# stm32103c8t6-v3.net
KiCad netlist of a schematic drawn in EAGLE
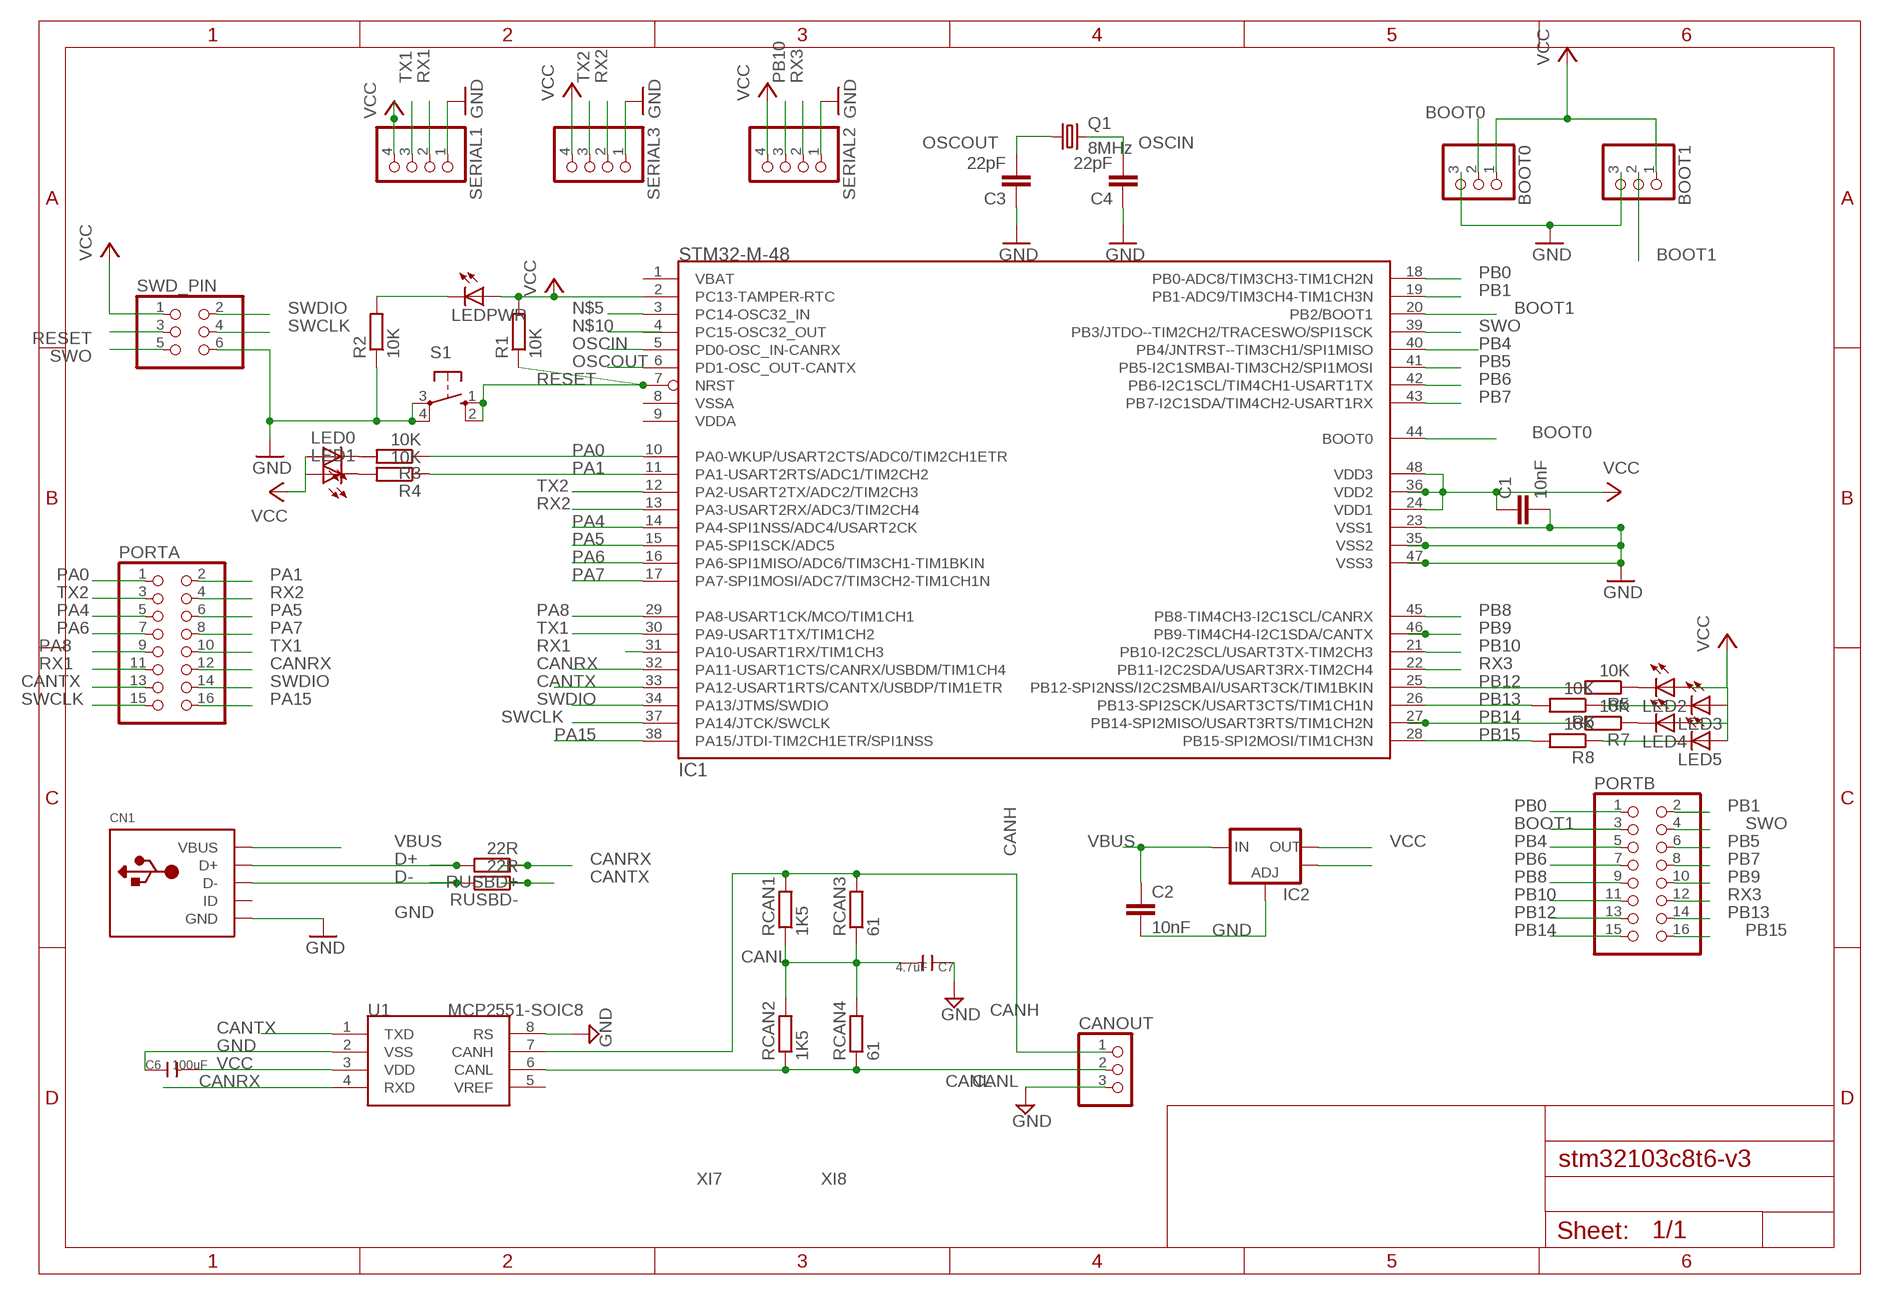
[diagram p0: schematic, sheet 1]

(export (version "E")
  (design (tool "Eeschema 10.0.6"))
  (components
    (comp (ref "BOOT0")
      (value "PINHD-1X3")
      (footprint "eagle-import:1X03")
      (libsource (lib "eagle-import") (part "PINHD-1X3"))
    )
    (comp (ref "BOOT1")
      (value "PINHD-1X3")
      (footprint "eagle-import:1X03")
      (libsource (lib "eagle-import") (part "PINHD-1X3"))
    )
    (comp (ref "C1")
      (value "10nF")
      (footprint "eagle-import:C1210")
      (libsource (lib "eagle-import") (part "C-EUC1210"))
    )
    (comp (ref "C2")
      (value "10nF")
      (footprint "eagle-import:C1206")
      (libsource (lib "eagle-import") (part "C-EUC1206"))
    )
    (comp (ref "C3")
      (value "22pF")
      (footprint "eagle-import:C1210")
      (libsource (lib "eagle-import") (part "C-EUC1210"))
    )
    (comp (ref "C4")
      (value "22pF")
      (footprint "eagle-import:C1210")
      (libsource (lib "eagle-import") (part "C-EUC1210"))
    )
    (comp (ref "C6")
      (value "100uF")
      (footprint "eagle-import:C1206")
      (libsource (lib "eagle-import") (part "C-1206"))
    )
    (comp (ref "C7")
      (value "4.7uF")
      (footprint "eagle-import:C1206")
      (libsource (lib "eagle-import") (part "C-1206"))
    )
    (comp (ref "CANOUT")
      (value "PINHD-1X3")
      (footprint "eagle-import:1X03")
      (libsource (lib "eagle-import") (part "PINHD-1X3"))
    )
    (comp (ref "CN1")
      (value "USBTHM")
      (footprint "eagle-import:USB-MINIB-THM")
      (libsource (lib "eagle-import") (part "USBTHM"))
    )
    (comp (ref "IC1")
      (value "STM32-M-48")
      (footprint "eagle-import:LQFP48")
      (libsource (lib "eagle-import") (part "STM32-M-48"))
    )
    (comp (ref "IC2")
      (value "V_REG_LM1117SOT223")
      (footprint "eagle-import:SOT223")
      (libsource (lib "eagle-import") (part "V_REG_LM1117SOT223"))
    )
    (comp (ref "LED0")
      (value "LEDSMT1206")
      (footprint "eagle-import:1206")
      (libsource (lib "eagle-import") (part "LEDSMT1206"))
    )
    (comp (ref "LED1")
      (value "LEDSMT1206")
      (footprint "eagle-import:1206")
      (libsource (lib "eagle-import") (part "LEDSMT1206"))
    )
    (comp (ref "LED2")
      (value "LEDSMT1206")
      (footprint "eagle-import:1206")
      (libsource (lib "eagle-import") (part "LEDSMT1206"))
    )
    (comp (ref "LED3")
      (value "LEDSMT1206")
      (footprint "eagle-import:1206")
      (libsource (lib "eagle-import") (part "LEDSMT1206"))
    )
    (comp (ref "LED4")
      (value "LEDSMT1206")
      (footprint "eagle-import:1206")
      (libsource (lib "eagle-import") (part "LEDSMT1206"))
    )
    (comp (ref "LED5")
      (value "LEDSMT1206")
      (footprint "eagle-import:1206")
      (libsource (lib "eagle-import") (part "LEDSMT1206"))
    )
    (comp (ref "LEDPWR")
      (value "LEDSMT1206")
      (footprint "eagle-import:1206")
      (libsource (lib "eagle-import") (part "LEDSMT1206"))
    )
    (comp (ref "PORTA")
      (value "PINHD-2X8")
      (footprint "eagle-import:2X08")
      (libsource (lib "eagle-import") (part "PINHD-2X8"))
    )
    (comp (ref "PORTB")
      (value "PINHD-2X8")
      (footprint "eagle-import:2X08")
      (libsource (lib "eagle-import") (part "PINHD-2X8"))
    )
    (comp (ref "Q1")
      (value "8MHz")
      (footprint "eagle-import:HC49_S")
      (libsource (lib "eagle-import") (part "CRYSTALHC49S"))
    )
    (comp (ref "R1")
      (value "10K")
      (footprint "eagle-import:R1206")
      (libsource (lib "eagle-import") (part "R-EU_R1206"))
    )
    (comp (ref "R2")
      (value "10K")
      (footprint "eagle-import:R1206")
      (libsource (lib "eagle-import") (part "R-EU_R1206"))
    )
    (comp (ref "R3")
      (value "10K")
      (footprint "eagle-import:R1206")
      (libsource (lib "eagle-import") (part "R-EU_R1206"))
    )
    (comp (ref "R4")
      (value "10K")
      (footprint "eagle-import:R1206")
      (libsource (lib "eagle-import") (part "R-EU_R1206"))
    )
    (comp (ref "R5")
      (value "10K")
      (footprint "eagle-import:R1206")
      (libsource (lib "eagle-import") (part "R-EU_R1206"))
    )
    (comp (ref "R6")
      (value "10K")
      (footprint "eagle-import:R1206")
      (libsource (lib "eagle-import") (part "R-EU_R1206"))
    )
    (comp (ref "R7")
      (value "10K")
      (footprint "eagle-import:R1206")
      (libsource (lib "eagle-import") (part "R-EU_R1206"))
    )
    (comp (ref "R8")
      (value "10K")
      (footprint "eagle-import:R1206")
      (libsource (lib "eagle-import") (part "R-EU_R1206"))
    )
    (comp (ref "RCAN1")
      (value "1K5")
      (footprint "eagle-import:R1206")
      (libsource (lib "eagle-import") (part "R-EU_R1206"))
    )
    (comp (ref "RCAN2")
      (value "1K5")
      (footprint "eagle-import:R1206")
      (libsource (lib "eagle-import") (part "R-EU_R1206"))
    )
    (comp (ref "RCAN3")
      (value "61")
      (footprint "eagle-import:R1206")
      (libsource (lib "eagle-import") (part "R-EU_R1206"))
    )
    (comp (ref "RCAN4")
      (value "61")
      (footprint "eagle-import:R1206")
      (libsource (lib "eagle-import") (part "R-EU_R1206"))
    )
    (comp (ref "RUSBD+")
      (value "22R")
      (footprint "eagle-import:R1206")
      (libsource (lib "eagle-import") (part "R-EU_R1206"))
    )
    (comp (ref "RUSBD-")
      (value "22R")
      (footprint "eagle-import:R1206")
      (libsource (lib "eagle-import") (part "R-EU_R1206"))
    )
    (comp (ref "S1")
      (value "10-XX")
      (footprint "eagle-import:B3F-10XX")
      (fields (field (name "MPN") "B3F-1000"))
      (libsource (lib "eagle-import") (part "10-XX"))
    )
    (comp (ref "SERIAL1")
      (value "PINHD-1X4")
      (footprint "eagle-import:1X04")
      (libsource (lib "eagle-import") (part "PINHD-1X4"))
    )
    (comp (ref "SERIAL2")
      (value "PINHD-1X4")
      (footprint "eagle-import:1X04")
      (libsource (lib "eagle-import") (part "PINHD-1X4"))
    )
    (comp (ref "SERIAL3")
      (value "PINHD-1X4")
      (footprint "eagle-import:1X04")
      (libsource (lib "eagle-import") (part "PINHD-1X4"))
    )
    (comp (ref "SWD_PIN")
      (value "PINHD-2X3")
      (footprint "eagle-import:2X03")
      (libsource (lib "eagle-import") (part "PINHD-2X3"))
    )
    (comp (ref "U1")
      (value "MCP2551-SOIC8")
      (footprint "eagle-import:SOIC8-6.0")
      (libsource (lib "eagle-import") (part "MCP2551-SOIC8"))
    )
  )
  (nets
    (net (code "1") (name "/BOOT0") (class "Default")
      (node (ref "BOOT0") (pin "2") (pinfunction "2_2") (pintype "passive"))
      (node (ref "IC1") (pin "44") (pinfunction "BOOT0_44") (pintype "input"))
    )
    (net (code "2") (name "/BOOT1") (class "Default")
      (node (ref "BOOT1") (pin "2") (pinfunction "2_2") (pintype "passive"))
      (node (ref "IC1") (pin "20") (pinfunction "PB2/BOOT1_20") (pintype "bidirectional"))
      (node (ref "PORTB") (pin "3") (pinfunction "3_3") (pintype "passive"))
    )
    (net (code "3") (name "/CANH") (class "Default")
      (node (ref "CANOUT") (pin "1") (pinfunction "1_1") (pintype "passive"))
      (node (ref "RCAN1") (pin "2") (pinfunction "2_2") (pintype "passive"))
      (node (ref "RCAN3") (pin "2") (pinfunction "2_2") (pintype "passive"))
      (node (ref "U1") (pin "7") (pinfunction "CANH_7") (pintype "bidirectional"))
    )
    (net (code "4") (name "/CANL") (class "Default")
      (node (ref "CANOUT") (pin "2") (pinfunction "2_2") (pintype "passive"))
      (node (ref "RCAN2") (pin "1") (pinfunction "1_1") (pintype "passive"))
      (node (ref "RCAN4") (pin "1") (pinfunction "1_1") (pintype "passive"))
      (node (ref "U1") (pin "6") (pinfunction "CANL_6") (pintype "bidirectional"))
    )
    (net (code "5") (name "/CANRX") (class "Default")
      (node (ref "IC1") (pin "32") (pinfunction "PA11-USART1CTS/CANRX/USBDM/TIM1CH4_32") (pintype "bidirectional"))
      (node (ref "PORTA") (pin "12") (pinfunction "12_12") (pintype "passive"))
      (node (ref "RUSBD+") (pin "1") (pinfunction "1_1") (pintype "passive"))
      (node (ref "U1") (pin "4") (pinfunction "RXD_4") (pintype "bidirectional"))
    )
    (net (code "6") (name "/CANTX") (class "Default")
      (node (ref "IC1") (pin "33") (pinfunction "PA12-USART1RTS/CANTX/USBDP/TIM1ETR_33") (pintype "bidirectional"))
      (node (ref "PORTA") (pin "13") (pinfunction "13_13") (pintype "passive"))
      (node (ref "RUSBD-") (pin "1") (pinfunction "1_1") (pintype "passive"))
      (node (ref "U1") (pin "1") (pinfunction "TXD_1") (pintype "bidirectional"))
    )
    (net (code "7") (name "/D+") (class "Default")
      (node (ref "CN1") (pin "D+") (pinfunction "D+_D+") (pintype "bidirectional"))
      (node (ref "RUSBD+") (pin "2") (pinfunction "2_2") (pintype "passive"))
    )
    (net (code "8") (name "/D-") (class "Default")
      (node (ref "CN1") (pin "D-") (pinfunction "D-_D-") (pintype "bidirectional"))
      (node (ref "RUSBD-") (pin "2") (pinfunction "2_2") (pintype "passive"))
    )
    (net (code "9") (name "/N$5") (class "Default")
      (node (ref "IC1") (pin "3") (pinfunction "PC14-OSC32_IN_3") (pintype "bidirectional"))
    )
    (net (code "11") (name "/OSCIN") (class "Default")
      (node (ref "C4") (pin "2") (pinfunction "2_2") (pintype "passive"))
      (node (ref "IC1") (pin "5") (pinfunction "PD0-OSC_IN-CANRX_5") (pintype "input"))
      (node (ref "Q1") (pin "2") (pinfunction "2_2") (pintype "passive"))
    )
    (net (code "12") (name "/OSCOUT") (class "Default")
      (node (ref "C3") (pin "2") (pinfunction "2_2") (pintype "passive"))
      (node (ref "IC1") (pin "6") (pinfunction "PD1-OSC_OUT-CANTX_6") (pintype "output"))
      (node (ref "Q1") (pin "1") (pinfunction "1_1") (pintype "passive"))
    )
    (net (code "13") (name "/PA0") (class "Default")
      (node (ref "IC1") (pin "10") (pinfunction "PA0-WKUP/USART2CTS/ADC0/TIM2CH1ETR_10") (pintype "bidirectional"))
      (node (ref "PORTA") (pin "1") (pinfunction "1_1") (pintype "passive"))
      (node (ref "R3") (pin "1") (pinfunction "1_1") (pintype "passive"))
    )
    (net (code "14") (name "/PA1") (class "Default")
      (node (ref "IC1") (pin "11") (pinfunction "PA1-USART2RTS/ADC1/TIM2CH2_11") (pintype "bidirectional"))
      (node (ref "PORTA") (pin "2") (pinfunction "2_2") (pintype "passive"))
      (node (ref "R4") (pin "1") (pinfunction "1_1") (pintype "passive"))
    )
    (net (code "15") (name "/PA4") (class "Default")
      (node (ref "IC1") (pin "14") (pinfunction "PA4-SPI1NSS/ADC4/USART2CK_14") (pintype "bidirectional"))
      (node (ref "PORTA") (pin "5") (pinfunction "5_5") (pintype "passive"))
    )
    (net (code "16") (name "/PA5") (class "Default")
      (node (ref "IC1") (pin "15") (pinfunction "PA5-SPI1SCK/ADC5_15") (pintype "bidirectional"))
      (node (ref "PORTA") (pin "6") (pinfunction "6_6") (pintype "passive"))
    )
    (net (code "17") (name "/PA6") (class "Default")
      (node (ref "IC1") (pin "16") (pinfunction "PA6-SPI1MISO/ADC6/TIM3CH1-TIM1BKIN_16") (pintype "bidirectional"))
      (node (ref "PORTA") (pin "7") (pinfunction "7_7") (pintype "passive"))
    )
    (net (code "18") (name "/PA7") (class "Default")
      (node (ref "IC1") (pin "17") (pinfunction "PA7-SPI1MOSI/ADC7/TIM3CH2-TIM1CH1N_17") (pintype "bidirectional"))
      (node (ref "PORTA") (pin "8") (pinfunction "8_8") (pintype "passive"))
    )
    (net (code "19") (name "/PA8") (class "Default")
      (node (ref "IC1") (pin "29") (pinfunction "PA8-USART1CK/MCO/TIM1CH1_29") (pintype "bidirectional"))
      (node (ref "PORTA") (pin "9") (pinfunction "9_9") (pintype "passive"))
    )
    (net (code "20") (name "/PA15") (class "Default")
      (node (ref "IC1") (pin "38") (pinfunction "PA15/JTDI-TIM2CH1ETR/SPI1NSS_38") (pintype "bidirectional"))
      (node (ref "PORTA") (pin "16") (pinfunction "16_16") (pintype "passive"))
    )
    (net (code "21") (name "/PB0") (class "Default")
      (node (ref "IC1") (pin "18") (pinfunction "PB0-ADC8/TIM3CH3-TIM1CH2N_18") (pintype "bidirectional"))
      (node (ref "PORTB") (pin "1") (pinfunction "1_1") (pintype "passive"))
    )
    (net (code "22") (name "/PB1") (class "Default")
      (node (ref "IC1") (pin "19") (pinfunction "PB1-ADC9/TIM3CH4-TIM1CH3N_19") (pintype "bidirectional"))
      (node (ref "PORTB") (pin "2") (pinfunction "2_2") (pintype "passive"))
    )
    (net (code "23") (name "/PB4") (class "Default")
      (node (ref "IC1") (pin "40") (pinfunction "PB4/JNTRST--TIM3CH1/SPI1MISO_40") (pintype "bidirectional"))
      (node (ref "PORTB") (pin "5") (pinfunction "5_5") (pintype "passive"))
    )
    (net (code "24") (name "/PB5") (class "Default")
      (node (ref "IC1") (pin "41") (pinfunction "PB5-I2C1SMBAI-TIM3CH2/SPI1MOSI_41") (pintype "bidirectional"))
      (node (ref "PORTB") (pin "6") (pinfunction "6_6") (pintype "passive"))
    )
    (net (code "25") (name "/PB6") (class "Default")
      (node (ref "IC1") (pin "42") (pinfunction "PB6-I2C1SCL/TIM4CH1-USART1TX_42") (pintype "bidirectional"))
      (node (ref "PORTB") (pin "7") (pinfunction "7_7") (pintype "passive"))
    )
    (net (code "26") (name "/PB7") (class "Default")
      (node (ref "IC1") (pin "43") (pinfunction "PB7-I2C1SDA/TIM4CH2-USART1RX_43") (pintype "bidirectional"))
      (node (ref "PORTB") (pin "8") (pinfunction "8_8") (pintype "passive"))
    )
    (net (code "27") (name "/PB8") (class "Default")
      (node (ref "IC1") (pin "45") (pinfunction "PB8-TIM4CH3-I2C1SCL/CANRX_45") (pintype "bidirectional"))
      (node (ref "PORTB") (pin "9") (pinfunction "9_9") (pintype "passive"))
    )
    (net (code "28") (name "/PB9") (class "Default")
      (node (ref "IC1") (pin "46") (pinfunction "PB9-TIM4CH4-I2C1SDA/CANTX_46") (pintype "bidirectional"))
      (node (ref "PORTB") (pin "10") (pinfunction "10_10") (pintype "passive"))
    )
    (net (code "29") (name "/PB10") (class "Default")
      (node (ref "IC1") (pin "21") (pinfunction "PB10-I2C2SCL/USART3TX-TIM2CH3_21") (pintype "bidirectional"))
      (node (ref "PORTB") (pin "11") (pinfunction "11_11") (pintype "passive"))
      (node (ref "SERIAL2") (pin "3") (pinfunction "3_3") (pintype "passive"))
    )
    (net (code "30") (name "/PB12") (class "Default")
      (node (ref "IC1") (pin "25") (pinfunction "PB12-SPI2NSS/I2C2SMBAI/USART3CK/TIM1BKIN_25") (pintype "bidirectional"))
      (node (ref "PORTB") (pin "13") (pinfunction "13_13") (pintype "passive"))
      (node (ref "R5") (pin "2") (pinfunction "2_2") (pintype "passive"))
    )
    (net (code "31") (name "/PB13") (class "Default")
      (node (ref "IC1") (pin "26") (pinfunction "PB13-SPI2SCK/USART3CTS/TIM1CH1N_26") (pintype "bidirectional"))
      (node (ref "PORTB") (pin "14") (pinfunction "14_14") (pintype "passive"))
      (node (ref "R6") (pin "2") (pinfunction "2_2") (pintype "passive"))
    )
    (net (code "32") (name "/PB14") (class "Default")
      (node (ref "IC1") (pin "27") (pinfunction "PB14-SPI2MISO/USART3RTS/TIM1CH2N_27") (pintype "bidirectional"))
      (node (ref "PORTB") (pin "15") (pinfunction "15_15") (pintype "passive"))
      (node (ref "R7") (pin "2") (pinfunction "2_2") (pintype "passive"))
    )
    (net (code "33") (name "/PB15") (class "Default")
      (node (ref "IC1") (pin "28") (pinfunction "PB15-SPI2MOSI/TIM1CH3N_28") (pintype "bidirectional"))
      (node (ref "PORTB") (pin "16") (pinfunction "16_16") (pintype "passive"))
      (node (ref "R8") (pin "2") (pinfunction "2_2") (pintype "passive"))
    )
    (net (code "34") (name "/RESET") (class "Default")
      (node (ref "IC1") (pin "7") (pinfunction "NRST_7") (pintype "bidirectional"))
      (node (ref "R1") (pin "1") (pinfunction "1_1") (pintype "passive"))
      (node (ref "S1") (pin "1") (pinfunction "S_1") (pintype "passive"))
      (node (ref "S1") (pin "2") (pinfunction "S1_2") (pintype "passive"))
      (node (ref "SWD_PIN") (pin "3") (pinfunction "3_3") (pintype "passive"))
    )
    (net (code "35") (name "/RX1") (class "Default")
      (node (ref "IC1") (pin "31") (pinfunction "PA10-USART1RX/TIM1CH3_31") (pintype "bidirectional"))
      (node (ref "PORTA") (pin "11") (pinfunction "11_11") (pintype "passive"))
      (node (ref "SERIAL1") (pin "2") (pinfunction "2_2") (pintype "passive"))
    )
    (net (code "36") (name "/RX2") (class "Default")
      (node (ref "IC1") (pin "13") (pinfunction "PA3-USART2RX/ADC3/TIM2CH4_13") (pintype "bidirectional"))
      (node (ref "PORTA") (pin "4") (pinfunction "4_4") (pintype "passive"))
      (node (ref "SERIAL3") (pin "2") (pinfunction "2_2") (pintype "passive"))
    )
    (net (code "37") (name "/RX3") (class "Default")
      (node (ref "IC1") (pin "22") (pinfunction "PB11-I2C2SDA/USART3RX-TIM2CH4_22") (pintype "bidirectional"))
      (node (ref "PORTB") (pin "12") (pinfunction "12_12") (pintype "passive"))
      (node (ref "SERIAL2") (pin "2") (pinfunction "2_2") (pintype "passive"))
    )
    (net (code "38") (name "/SWCLK") (class "Default")
      (node (ref "IC1") (pin "37") (pinfunction "PA14/JTCK/SWCLK_37") (pintype "bidirectional"))
      (node (ref "PORTA") (pin "15") (pinfunction "15_15") (pintype "passive"))
      (node (ref "SWD_PIN") (pin "4") (pinfunction "4_4") (pintype "passive"))
    )
    (net (code "39") (name "/SWDIO") (class "Default")
      (node (ref "IC1") (pin "34") (pinfunction "PA13/JTMS/SWDIO_34") (pintype "bidirectional"))
      (node (ref "PORTA") (pin "14") (pinfunction "14_14") (pintype "passive"))
      (node (ref "SWD_PIN") (pin "2") (pinfunction "2_2") (pintype "passive"))
    )
    (net (code "40") (name "/SWO") (class "Default")
      (node (ref "IC1") (pin "39") (pinfunction "PB3/JTDO--TIM2CH2/TRACESWO/SPI1SCK_39") (pintype "bidirectional"))
      (node (ref "PORTB") (pin "4") (pinfunction "4_4") (pintype "passive"))
      (node (ref "SWD_PIN") (pin "5") (pinfunction "5_5") (pintype "passive"))
    )
    (net (code "41") (name "/TX1") (class "Default")
      (node (ref "IC1") (pin "30") (pinfunction "PA9-USART1TX/TIM1CH2_30") (pintype "bidirectional"))
      (node (ref "PORTA") (pin "10") (pinfunction "10_10") (pintype "passive"))
      (node (ref "SERIAL1") (pin "3") (pinfunction "3_3") (pintype "passive"))
    )
    (net (code "42") (name "/TX2") (class "Default")
      (node (ref "IC1") (pin "12") (pinfunction "PA2-USART2TX/ADC2/TIM2CH3_12") (pintype "bidirectional"))
      (node (ref "PORTA") (pin "3") (pinfunction "3_3") (pintype "passive"))
      (node (ref "SERIAL3") (pin "3") (pinfunction "3_3") (pintype "passive"))
    )
    (net (code "43") (name "/VBAT") (class "Default")
      (node (ref "IC1") (pin "1") (pinfunction "VBAT_1") (pintype "power_in"))
    )
    (net (code "44") (name "/VBUS") (class "Default")
      (node (ref "C2") (pin "1") (pinfunction "1_1") (pintype "passive"))
      (node (ref "CN1") (pin "VBUS") (pinfunction "VBUS_VBUS") (pintype "power_in"))
      (node (ref "IC2") (pin "3") (pinfunction "IN_3") (pintype "input"))
    )
    (net (code "45") (name "/VDDA") (class "Default")
      (node (ref "IC1") (pin "9") (pinfunction "VDDA_9") (pintype "power_in"))
    )
    (net (code "46") (name "/VSSA") (class "Default")
      (node (ref "IC1") (pin "8") (pinfunction "VSSA_8") (pintype "power_in"))
    )
    (net (code "49") (name "GND") (class "Default")
      (node (ref "BOOT0") (pin "3") (pinfunction "3_3") (pintype "passive"))
      (node (ref "BOOT1") (pin "3") (pinfunction "3_3") (pintype "passive"))
      (node (ref "C1") (pin "2") (pinfunction "2_2") (pintype "passive"))
      (node (ref "C2") (pin "2") (pinfunction "2_2") (pintype "passive"))
      (node (ref "C3") (pin "1") (pinfunction "1_1") (pintype "passive"))
      (node (ref "C4") (pin "1") (pinfunction "1_1") (pintype "passive"))
      (node (ref "C6") (pin "1") (pinfunction "1_1") (pintype "passive"))
      (node (ref "C7") (pin "1") (pinfunction "1_1") (pintype "passive"))
      (node (ref "CANOUT") (pin "3") (pinfunction "3_3") (pintype "passive"))
      (node (ref "CN1") (pin "GND") (pinfunction "GND_GND") (pintype "power_in"))
      (node (ref "IC1") (pin "23") (pinfunction "VSS1_23") (pintype "power_in"))
      (node (ref "IC1") (pin "35") (pinfunction "VSS2_35") (pintype "power_in"))
      (node (ref "IC1") (pin "47") (pinfunction "VSS3_47") (pintype "power_in"))
      (node (ref "IC2") (pin "1") (pinfunction "ADJ_1") (pintype "input"))
      (node (ref "R2") (pin "1") (pinfunction "1_1") (pintype "passive"))
      (node (ref "S1") (pin "3") (pinfunction "P_3") (pintype "passive"))
      (node (ref "S1") (pin "4") (pinfunction "P1_4") (pintype "passive"))
      (node (ref "SERIAL1") (pin "1") (pinfunction "1_1") (pintype "passive"))
      (node (ref "SERIAL2") (pin "1") (pinfunction "1_1") (pintype "passive"))
      (node (ref "SERIAL3") (pin "1") (pinfunction "1_1") (pintype "passive"))
      (node (ref "SWD_PIN") (pin "6") (pinfunction "6_6") (pintype "passive"))
      (node (ref "U1") (pin "2") (pinfunction "VSS_2") (pintype "bidirectional"))
      (node (ref "U1") (pin "8") (pinfunction "RS_8") (pintype "bidirectional"))
    )
    (net (code "50") (name "Net-(C7-Pad2)") (class "Default")
      (node (ref "C7") (pin "2") (pinfunction "2_2") (pintype "passive"))
      (node (ref "RCAN1") (pin "1") (pinfunction "1_1") (pintype "passive"))
      (node (ref "RCAN2") (pin "2") (pinfunction "2_2") (pintype "passive"))
      (node (ref "RCAN3") (pin "1") (pinfunction "1_1") (pintype "passive"))
      (node (ref "RCAN4") (pin "2") (pinfunction "2_2") (pintype "passive"))
    )
    (net (code "51") (name "Net-(LED0-PadC)") (class "Default")
      (node (ref "LED0") (pin "C") (pinfunction "C_C") (pintype "passive"))
      (node (ref "R3") (pin "2") (pinfunction "2_2") (pintype "passive"))
    )
    (net (code "52") (name "Net-(LED1-PadC)") (class "Default")
      (node (ref "LED1") (pin "C") (pinfunction "C_C") (pintype "passive"))
      (node (ref "R4") (pin "2") (pinfunction "2_2") (pintype "passive"))
    )
    (net (code "53") (name "Net-(LED2-PadC)") (class "Default")
      (node (ref "LED2") (pin "C") (pinfunction "C_C") (pintype "passive"))
      (node (ref "R5") (pin "1") (pinfunction "1_1") (pintype "passive"))
    )
    (net (code "54") (name "Net-(LED3-PadC)") (class "Default")
      (node (ref "LED3") (pin "C") (pinfunction "C_C") (pintype "passive"))
      (node (ref "R6") (pin "1") (pinfunction "1_1") (pintype "passive"))
    )
    (net (code "55") (name "Net-(LED4-PadC)") (class "Default")
      (node (ref "LED4") (pin "C") (pinfunction "C_C") (pintype "passive"))
      (node (ref "R7") (pin "1") (pinfunction "1_1") (pintype "passive"))
    )
    (net (code "56") (name "Net-(LED5-PadC)") (class "Default")
      (node (ref "LED5") (pin "C") (pinfunction "C_C") (pintype "passive"))
      (node (ref "R8") (pin "1") (pinfunction "1_1") (pintype "passive"))
    )
    (net (code "57") (name "Net-(LEDPWR-PadC)") (class "Default")
      (node (ref "LEDPWR") (pin "C") (pinfunction "C_C") (pintype "passive"))
      (node (ref "R2") (pin "2") (pinfunction "2_2") (pintype "passive"))
    )
    (net (code "58") (name "VCC") (class "Default")
      (node (ref "BOOT0") (pin "1") (pinfunction "1_1") (pintype "passive"))
      (node (ref "BOOT1") (pin "1") (pinfunction "1_1") (pintype "passive"))
      (node (ref "C1") (pin "1") (pinfunction "1_1") (pintype "passive"))
      (node (ref "C6") (pin "2") (pinfunction "2_2") (pintype "passive"))
      (node (ref "IC1") (pin "2") (pinfunction "PC13-TAMPER-RTC_2") (pintype "bidirectional"))
      (node (ref "IC1") (pin "24") (pinfunction "VDD1_24") (pintype "power_in"))
      (node (ref "IC1") (pin "36") (pinfunction "VDD2_36") (pintype "power_in"))
      (node (ref "IC1") (pin "48") (pinfunction "VDD3_48") (pintype "power_in"))
      (node (ref "IC2") (pin "2") (pinfunction "OUT_2") (pintype "output"))
      (node (ref "LED0") (pin "A") (pinfunction "A_A") (pintype "passive"))
      (node (ref "LED1") (pin "A") (pinfunction "A_A") (pintype "passive"))
      (node (ref "LED2") (pin "A") (pinfunction "A_A") (pintype "passive"))
      (node (ref "LED3") (pin "A") (pinfunction "A_A") (pintype "passive"))
      (node (ref "LED4") (pin "A") (pinfunction "A_A") (pintype "passive"))
      (node (ref "LED5") (pin "A") (pinfunction "A_A") (pintype "passive"))
      (node (ref "LEDPWR") (pin "A") (pinfunction "A_A") (pintype "passive"))
      (node (ref "R1") (pin "2") (pinfunction "2_2") (pintype "passive"))
      (node (ref "SERIAL1") (pin "4") (pinfunction "4_4") (pintype "passive"))
      (node (ref "SERIAL2") (pin "4") (pinfunction "4_4") (pintype "passive"))
      (node (ref "SERIAL3") (pin "4") (pinfunction "4_4") (pintype "passive"))
      (node (ref "SWD_PIN") (pin "1") (pinfunction "1_1") (pintype "passive"))
      (node (ref "U1") (pin "3") (pinfunction "VDD_3") (pintype "bidirectional"))
    )
    (net (code "59") (name "unconnected-(CN1-PadID)") (class "Default")
      (node (ref "CN1") (pin "ID") (pinfunction "ID_ID") (pintype "bidirectional"))
    )
    (net (code "60") (name "unconnected-(IC1-PC15-OSC32_OUT-Pad4)") (class "Default")
      (node (ref "IC1") (pin "4") (pinfunction "PC15-OSC32_OUT_4") (pintype "bidirectional"))
    )
    (net (code "61") (name "unconnected-(IC2-OUT-Pad4)") (class "Default")
      (node (ref "IC2") (pin "4") (pinfunction "OUT_4") (pintype "output"))
    )
    (net (code "62") (name "unconnected-(U1-VREF-Pad5)") (class "Default")
      (node (ref "U1") (pin "5") (pinfunction "VREF_5") (pintype "bidirectional"))
    )
  )
)
